# DigitalandPWR.net
KiCad netlist of a schematic drawn in Altium Designer
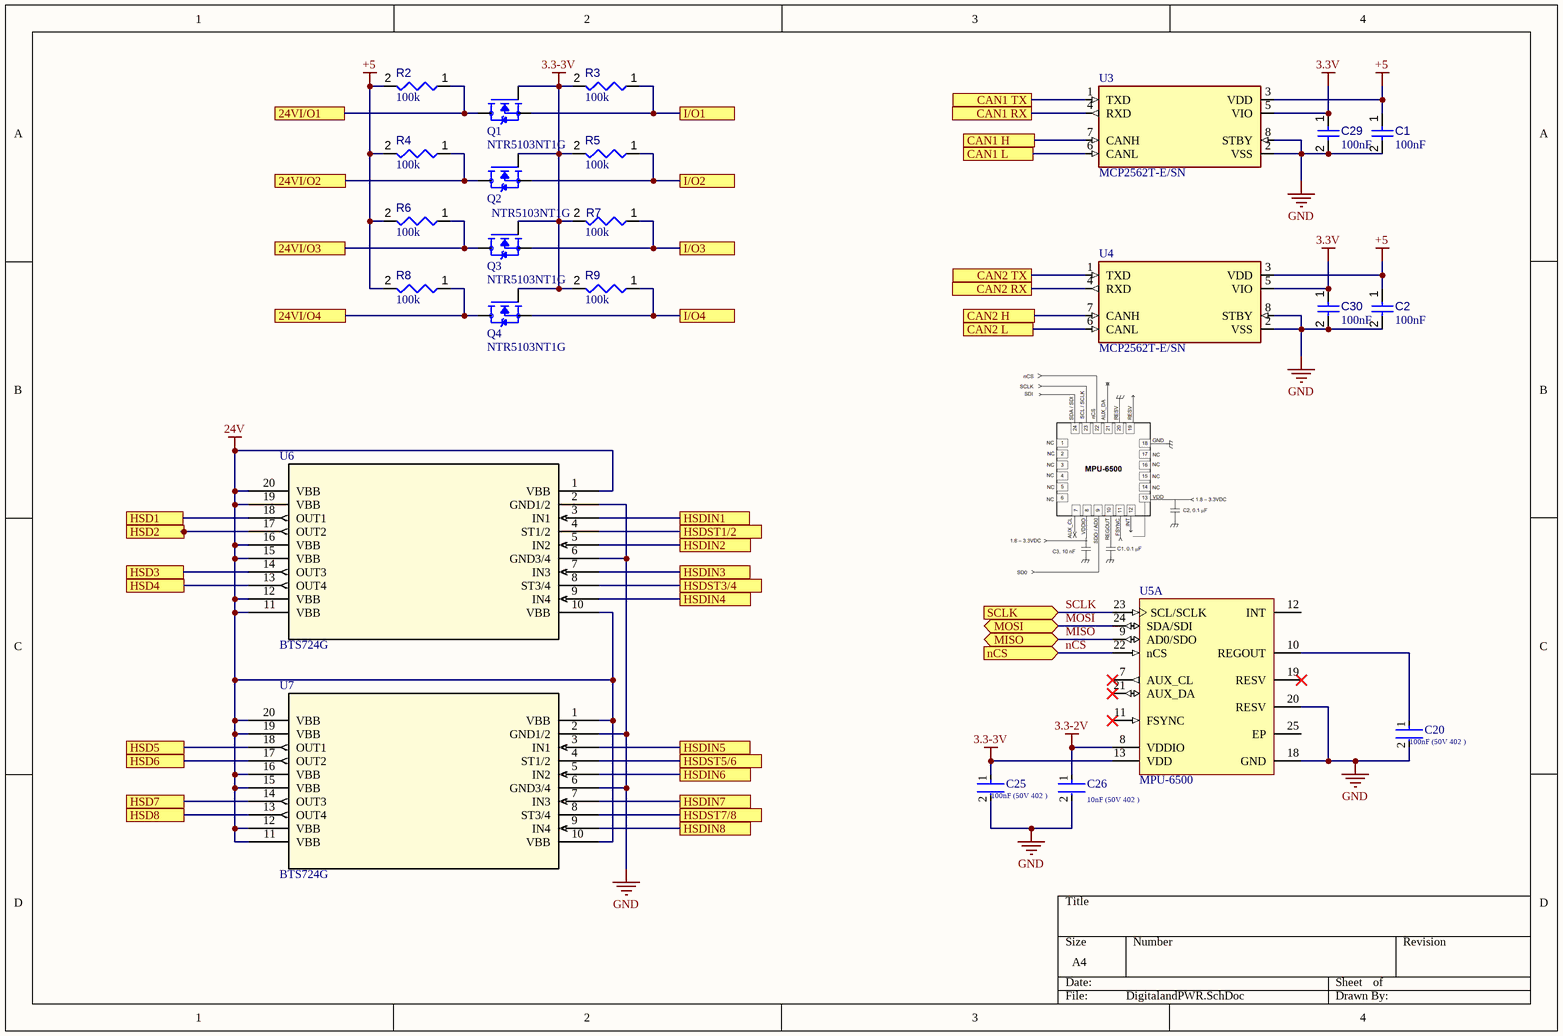
[diagram p0: DigitalandPWR.SchDoc]

(export (version "E")
  (design (tool "Eeschema 10.0.6"))
  (components
    (comp (ref "C1")
      (value "100nF")
      (footprint "CAPC0402(1005)60_L")
      (description "Chip Capacitor, 100nF +/-20%, 25V, 0402, Thickness 0.6 mm")
      (fields (field (name "TOLERANCE") "10%") (field (name "Comment") "Capacitor 100nF +/-20% 25V 0402"))
      (libsource (lib "Western Formula Racing") (part "CAP-NP-2"))
    )
    (comp (ref "C2")
      (value "100nF")
      (footprint "CAPC0402(1005)60_L")
      (description "Chip Capacitor, 100nF +/-20%, 25V, 0402, Thickness 0.6 mm")
      (fields (field (name "TOLERANCE") "10%") (field (name "Comment") "Capacitor 100nF +/-20% 25V 0402"))
      (libsource (lib "Western Formula Racing") (part "CAP-NP-2"))
    )
    (comp (ref "C20")
      (value "100nF (50V 402 )")
      (footprint "FP-CL779-IPC_C")
      (description "Cap Ceramic 100nF 50V X7R ±10% SMD 0402 +125°C Paper T/R")
      (libsource (lib "Altium Content Vault") (part "b4654b650e69147ec39a6b967a45e02"))
    )
    (comp (ref "C25")
      (value "100nF (50V 402 )")
      (footprint "FP-CL779-IPC_C")
      (description "Cap Ceramic 100nF 50V X7R ±10% SMD 0402 +125°C Paper T/R")
      (libsource (lib "Altium Content Vault") (part "b4654b650e69147ec39a6b967a45e02"))
    )
    (comp (ref "C26")
      (value "10nF (50V 402 )")
      (footprint "FP-CL165-IPC_C")
      (description "Cap Ceramic 10nF 50V X7R ±10% SMD 0402 +125°C Paper T/R")
      (fields (field (name "VOLTAGE") "50V") (field (name "TOLERANCE") "10%"))
      (libsource (lib "Altium Content Vault") (part "b4654b650e69147ec39a6b967a45e02"))
    )
    (comp (ref "C29")
      (value "100nF")
      (footprint "CAPC0402(1005)60_L")
      (description "Chip Capacitor, 100nF +/-20%, 25V, 0402, Thickness 0.6 mm")
      (fields (field (name "TOLERANCE") "10%") (field (name "Comment") "Capacitor 100nF +/-20% 25V 0402"))
      (libsource (lib "Western Formula Racing") (part "CAP-NP-2"))
    )
    (comp (ref "C30")
      (value "100nF")
      (footprint "CAPC0402(1005)60_L")
      (description "Chip Capacitor, 100nF +/-20%, 25V, 0402, Thickness 0.6 mm")
      (fields (field (name "TOLERANCE") "10%") (field (name "Comment") "Capacitor 100nF +/-20% 25V 0402"))
      (libsource (lib "Western Formula Racing") (part "CAP-NP-2"))
    )
    (comp (ref "Q1")
      (value "NTR5103NT1G")
      (footprint "SOT95P237X111-3N")
      (description "N-Channel 60V 260mA _Ta_ 300mW _Ta_ Surface Mount SOT-23-3 _TO-236_")
      (fields (field (name "MF") "ON Semiconductor"))
      (libsource (lib "Western Formula Racing") (part "NTR5103NT1G"))
    )
    (comp (ref "Q2")
      (value "NTR5103NT1G")
      (footprint "SOT95P237X111-3N")
      (description "N-Channel 60V 260mA _Ta_ 300mW _Ta_ Surface Mount SOT-23-3 _TO-236_")
      (fields (field (name "MF") "ON Semiconductor"))
      (libsource (lib "Western Formula Racing") (part "NTR5103NT1G"))
    )
    (comp (ref "Q3")
      (value "NTR5103NT1G")
      (footprint "SOT95P237X111-3N")
      (description "N-Channel 60V 260mA _Ta_ 300mW _Ta_ Surface Mount SOT-23-3 _TO-236_")
      (fields (field (name "MF") "ON Semiconductor"))
      (libsource (lib "Western Formula Racing") (part "NTR5103NT1G"))
    )
    (comp (ref "Q4")
      (value "NTR5103NT1G")
      (footprint "SOT95P237X111-3N")
      (description "N-Channel 60V 260mA _Ta_ 300mW _Ta_ Surface Mount SOT-23-3 _TO-236_")
      (fields (field (name "MF") "ON Semiconductor"))
      (libsource (lib "Western Formula Racing") (part "NTR5103NT1G"))
    )
    (comp (ref "R2")
      (value "100k")
      (footprint "RESC0402(1005)_L")
      (description "Chip Resistor, 100 kOhms, +/-1 %, 63 mW, -55 to 155 degC, 0402")
      (fields (field (name "TOLERANCE") "1%") (field (name "POWER") "63mW"))
      (libsource (lib "Western Formula Racing") (part "RES-2"))
    )
    (comp (ref "R3")
      (value "100k")
      (footprint "RESC0402(1005)_L")
      (description "Chip Resistor, 100 kOhms, +/-1 %, 63 mW, -55 to 155 degC, 0402")
      (fields (field (name "TOLERANCE") "1%") (field (name "POWER") "63mW"))
      (libsource (lib "Western Formula Racing") (part "RES-2"))
    )
    (comp (ref "R4")
      (value "100k")
      (footprint "RESC0402(1005)_L")
      (description "Chip Resistor, 100 kOhms, +/-1 %, 63 mW, -55 to 155 degC, 0402")
      (fields (field (name "TOLERANCE") "1%") (field (name "POWER") "63mW"))
      (libsource (lib "Western Formula Racing") (part "RES-2"))
    )
    (comp (ref "R5")
      (value "100k")
      (footprint "RESC0402(1005)_L")
      (description "Chip Resistor, 100 kOhms, +/-1 %, 63 mW, -55 to 155 degC, 0402")
      (fields (field (name "TOLERANCE") "1%") (field (name "POWER") "63mW"))
      (libsource (lib "Western Formula Racing") (part "RES-2"))
    )
    (comp (ref "R6")
      (value "100k")
      (footprint "RESC0402(1005)_L")
      (description "Chip Resistor, 100 kOhms, +/-1 %, 63 mW, -55 to 155 degC, 0402")
      (fields (field (name "TOLERANCE") "1%") (field (name "POWER") "63mW"))
      (libsource (lib "Western Formula Racing") (part "RES-2"))
    )
    (comp (ref "R7")
      (value "100k")
      (footprint "RESC0402(1005)_L")
      (description "Chip Resistor, 100 kOhms, +/-1 %, 63 mW, -55 to 155 degC, 0402")
      (fields (field (name "TOLERANCE") "1%") (field (name "POWER") "63mW"))
      (libsource (lib "Western Formula Racing") (part "RES-2"))
    )
    (comp (ref "R8")
      (value "100k")
      (footprint "RESC0402(1005)_L")
      (description "Chip Resistor, 100 kOhms, +/-1 %, 63 mW, -55 to 155 degC, 0402")
      (fields (field (name "TOLERANCE") "1%") (field (name "POWER") "63mW"))
      (libsource (lib "Western Formula Racing") (part "RES-2"))
    )
    (comp (ref "R9")
      (value "100k")
      (footprint "RESC0402(1005)_L")
      (description "Chip Resistor, 100 kOhms, +/-1 %, 63 mW, -55 to 155 degC, 0402")
      (fields (field (name "TOLERANCE") "1%") (field (name "POWER") "63mW"))
      (libsource (lib "Western Formula Racing") (part "RES-2"))
    )
    (comp (ref "U3")
      (value "MCP2562T-E/SN")
      (footprint "SOIC127P600X175-8N")
      (description "1/1 Transceiver Half CANbus 8-SOIC")
      (fields (field (name "DIGI-KEY_PART_NUMBER") "MCP2562T-E/SNCT-ND") (field (name "MF") "Microchip"))
      (libsource (lib "Western Formula Racing") (part "MCP2562T-E/SN"))
    )
    (comp (ref "U4")
      (value "MCP2562T-E/SN")
      (footprint "SOIC127P600X175-8N")
      (description "1/1 Transceiver Half CANbus 8-SOIC")
      (fields (field (name "DIGI-KEY_PART_NUMBER") "MCP2562T-E/SNCT-ND") (field (name "MF") "Microchip"))
      (libsource (lib "Western Formula Racing") (part "MCP2562T-E/SN"))
    )
    (comp (ref "U5")
      (value "MPU-6500")
      (footprint "INSE-MPU-6500-QFN24_M")
      (fields (field (name "MANUFACTURER") "InvenSense"))
      (libsource (lib "Altium Content Vault") (part "INSE-MPU-6500-24"))
    )
    (comp (ref "U6")
      (value "BTS724G")
      (footprint "SOIC-20_INF")
      (description "No Description Available")
      (fields (field (name "COPYRIGHT") "Copyright (C) 2023 Ultra Librarian. All rights reserved."))
      (libsource (lib "Western Formula Racing") (part "BTS724G"))
    )
    (comp (ref "U7")
      (value "BTS724G")
      (footprint "SOIC-20_INF")
      (description "No Description Available")
      (fields (field (name "COPYRIGHT") "Copyright (C) 2023 Ultra Librarian. All rights reserved."))
      (libsource (lib "Western Formula Racing") (part "BTS724G"))
    )
  )
  (nets
    (net (code "1") (name "+5") (class "Default")
      (node (ref "C1") (pin "1") (pinfunction "1_1") (pintype "passive"))
      (node (ref "C2") (pin "1") (pinfunction "1_1") (pintype "passive"))
      (node (ref "R2") (pin "2") (pinfunction "2_2") (pintype "passive"))
      (node (ref "R4") (pin "2") (pinfunction "2_2") (pintype "passive"))
      (node (ref "R6") (pin "2") (pinfunction "2_2") (pintype "passive"))
      (node (ref "R8") (pin "2") (pinfunction "2_2") (pintype "passive"))
      (node (ref "U3") (pin "3") (pinfunction "VDD_3") (pintype "power_in"))
      (node (ref "U4") (pin "3") (pinfunction "VDD_3") (pintype "power_in"))
    )
    (net (code "2") (name "/24VI{slash}O1") (class "Default")
      (node (ref "Q1") (pin "3") (pinfunction "D_3") (pintype "passive"))
      (node (ref "R2") (pin "1") (pinfunction "1_1") (pintype "passive"))
    )
    (net (code "3") (name "/24VI{slash}O2") (class "Default")
      (node (ref "Q2") (pin "3") (pinfunction "D_3") (pintype "passive"))
      (node (ref "R4") (pin "1") (pinfunction "1_1") (pintype "passive"))
    )
    (net (code "4") (name "/24VI{slash}O3") (class "Default")
      (node (ref "Q3") (pin "3") (pinfunction "D_3") (pintype "passive"))
      (node (ref "R6") (pin "1") (pinfunction "1_1") (pintype "passive"))
    )
    (net (code "5") (name "/24VI{slash}O4") (class "Default")
      (node (ref "Q4") (pin "3") (pinfunction "D_3") (pintype "passive"))
      (node (ref "R8") (pin "1") (pinfunction "1_1") (pintype "passive"))
    )
    (net (code "6") (name "/CAN1 H") (class "Default")
      (node (ref "U3") (pin "7") (pinfunction "CANH_7") (pintype "input"))
    )
    (net (code "7") (name "/CAN1 L") (class "Default")
      (node (ref "U3") (pin "6") (pinfunction "CANL_6") (pintype "input"))
    )
    (net (code "8") (name "/CAN1 RX") (class "Default")
      (node (ref "U3") (pin "4") (pinfunction "RXD_4") (pintype "output"))
    )
    (net (code "9") (name "/CAN1 TX") (class "Default")
      (node (ref "U3") (pin "1") (pinfunction "TXD_1") (pintype "input"))
    )
    (net (code "10") (name "/CAN2 H") (class "Default")
      (node (ref "U4") (pin "7") (pinfunction "CANH_7") (pintype "input"))
    )
    (net (code "11") (name "/CAN2 L") (class "Default")
      (node (ref "U4") (pin "6") (pinfunction "CANL_6") (pintype "input"))
    )
    (net (code "12") (name "/CAN2 RX") (class "Default")
      (node (ref "U4") (pin "4") (pinfunction "RXD_4") (pintype "output"))
    )
    (net (code "13") (name "/CAN2 TX") (class "Default")
      (node (ref "U4") (pin "1") (pinfunction "TXD_1") (pintype "input"))
    )
    (net (code "14") (name "/HSD1") (class "Default")
      (node (ref "U6") (pin "18") (pinfunction "OUT1_18") (pintype "output"))
    )
    (net (code "15") (name "/HSD2") (class "Default")
      (node (ref "U6") (pin "17") (pinfunction "OUT2_17") (pintype "output"))
    )
    (net (code "16") (name "/HSD3") (class "Default")
      (node (ref "U6") (pin "14") (pinfunction "OUT3_14") (pintype "output"))
    )
    (net (code "17") (name "/HSD4") (class "Default")
      (node (ref "U6") (pin "13") (pinfunction "OUT4_13") (pintype "output"))
    )
    (net (code "18") (name "/HSD5") (class "Default")
      (node (ref "U7") (pin "18") (pinfunction "OUT1_18") (pintype "output"))
    )
    (net (code "19") (name "/HSD6") (class "Default")
      (node (ref "U7") (pin "17") (pinfunction "OUT2_17") (pintype "output"))
    )
    (net (code "20") (name "/HSD7") (class "Default")
      (node (ref "U7") (pin "14") (pinfunction "OUT3_14") (pintype "output"))
    )
    (net (code "21") (name "/HSD8") (class "Default")
      (node (ref "U7") (pin "13") (pinfunction "OUT4_13") (pintype "output"))
    )
    (net (code "22") (name "/HSDIN1") (class "Default")
      (node (ref "U6") (pin "3") (pinfunction "IN1_3") (pintype "input"))
    )
    (net (code "23") (name "/HSDIN2") (class "Default")
      (node (ref "U6") (pin "5") (pinfunction "IN2_5") (pintype "input"))
    )
    (net (code "24") (name "/HSDIN3") (class "Default")
      (node (ref "U6") (pin "7") (pinfunction "IN3_7") (pintype "input"))
    )
    (net (code "25") (name "/HSDIN4") (class "Default")
      (node (ref "U6") (pin "9") (pinfunction "IN4_9") (pintype "input"))
    )
    (net (code "26") (name "/HSDIN5") (class "Default")
      (node (ref "U7") (pin "3") (pinfunction "IN1_3") (pintype "input"))
    )
    (net (code "27") (name "/HSDIN6") (class "Default")
      (node (ref "U7") (pin "5") (pinfunction "IN2_5") (pintype "input"))
    )
    (net (code "28") (name "/HSDIN7") (class "Default")
      (node (ref "U7") (pin "7") (pinfunction "IN3_7") (pintype "input"))
    )
    (net (code "29") (name "/HSDIN8") (class "Default")
      (node (ref "U7") (pin "9") (pinfunction "IN4_9") (pintype "input"))
    )
    (net (code "30") (name "/HSDST1{slash}2") (class "Default")
      (node (ref "U6") (pin "4") (pinfunction "ST1/2_4") (pintype "passive"))
    )
    (net (code "31") (name "/HSDST3{slash}4") (class "Default")
      (node (ref "U6") (pin "8") (pinfunction "ST3/4_8") (pintype "passive"))
    )
    (net (code "32") (name "/HSDST5{slash}6") (class "Default")
      (node (ref "U7") (pin "4") (pinfunction "ST1/2_4") (pintype "passive"))
    )
    (net (code "33") (name "/HSDST7{slash}8") (class "Default")
      (node (ref "U7") (pin "8") (pinfunction "ST3/4_8") (pintype "passive"))
    )
    (net (code "34") (name "/I{slash}O1") (class "Default")
      (node (ref "Q1") (pin "2") (pinfunction "S_2") (pintype "passive"))
      (node (ref "R3") (pin "1") (pinfunction "1_1") (pintype "passive"))
    )
    (net (code "35") (name "/I{slash}O2") (class "Default")
      (node (ref "Q2") (pin "2") (pinfunction "S_2") (pintype "passive"))
      (node (ref "R5") (pin "1") (pinfunction "1_1") (pintype "passive"))
    )
    (net (code "36") (name "/I{slash}O3") (class "Default")
      (node (ref "Q3") (pin "2") (pinfunction "S_2") (pintype "passive"))
      (node (ref "R7") (pin "1") (pinfunction "1_1") (pintype "passive"))
    )
    (net (code "37") (name "/I{slash}O4") (class "Default")
      (node (ref "Q4") (pin "2") (pinfunction "S_2") (pintype "passive"))
      (node (ref "R9") (pin "1") (pinfunction "1_1") (pintype "passive"))
    )
    (net (code "38") (name "/MISO") (class "Default")
      (node (ref "U5") (pin "9") (pinfunction "AD0/SDO_9") (pintype "bidirectional"))
    )
    (net (code "39") (name "/MOSI") (class "Default")
      (node (ref "U5") (pin "24") (pinfunction "SDA/SDI_24") (pintype "bidirectional"))
    )
    (net (code "40") (name "/SCLK") (class "Default")
      (node (ref "U5") (pin "23") (pinfunction "SCL/SCLK_23") (pintype "input"))
    )
    (net (code "41") (name "/nCS") (class "Default")
      (node (ref "U5") (pin "22") (pinfunction "nCS_22") (pintype "input"))
    )
    (net (code "42") (name "3.3-2V") (class "Default")
      (node (ref "C26") (pin "1") (pinfunction "1_1") (pintype "passive"))
      (node (ref "U5") (pin "8") (pinfunction "VDDIO_8") (pintype "power_in"))
    )
    (net (code "43") (name "3.3-3V") (class "Default")
      (node (ref "C25") (pin "1") (pinfunction "1_1") (pintype "passive"))
      (node (ref "Q1") (pin "1") (pinfunction "G_1") (pintype "passive"))
      (node (ref "Q2") (pin "1") (pinfunction "G_1") (pintype "passive"))
      (node (ref "Q3") (pin "1") (pinfunction "G_1") (pintype "passive"))
      (node (ref "Q4") (pin "1") (pinfunction "G_1") (pintype "passive"))
      (node (ref "R3") (pin "2") (pinfunction "2_2") (pintype "passive"))
      (node (ref "R5") (pin "2") (pinfunction "2_2") (pintype "passive"))
      (node (ref "R7") (pin "2") (pinfunction "2_2") (pintype "passive"))
      (node (ref "R9") (pin "2") (pinfunction "2_2") (pintype "passive"))
      (node (ref "U5") (pin "13") (pinfunction "VDD_13") (pintype "power_in"))
    )
    (net (code "44") (name "3.3V") (class "Default")
      (node (ref "C29") (pin "1") (pinfunction "1_1") (pintype "passive"))
      (node (ref "C30") (pin "1") (pinfunction "1_1") (pintype "passive"))
      (node (ref "U3") (pin "5") (pinfunction "VIO_5") (pintype "power_in"))
      (node (ref "U4") (pin "5") (pinfunction "VIO_5") (pintype "power_in"))
    )
    (net (code "45") (name "24V") (class "Default")
      (node (ref "U6") (pin "1") (pinfunction "VBB_1") (pintype "power_in"))
      (node (ref "U6") (pin "10") (pinfunction "VBB_10") (pintype "power_in"))
      (node (ref "U6") (pin "11") (pinfunction "VBB_11") (pintype "power_in"))
      (node (ref "U6") (pin "12") (pinfunction "VBB_12") (pintype "power_in"))
      (node (ref "U6") (pin "15") (pinfunction "VBB_15") (pintype "power_in"))
      (node (ref "U6") (pin "16") (pinfunction "VBB_16") (pintype "power_in"))
      (node (ref "U6") (pin "19") (pinfunction "VBB_19") (pintype "power_in"))
      (node (ref "U6") (pin "20") (pinfunction "VBB_20") (pintype "power_in"))
      (node (ref "U7") (pin "1") (pinfunction "VBB_1") (pintype "power_in"))
      (node (ref "U7") (pin "10") (pinfunction "VBB_10") (pintype "power_in"))
      (node (ref "U7") (pin "11") (pinfunction "VBB_11") (pintype "power_in"))
      (node (ref "U7") (pin "12") (pinfunction "VBB_12") (pintype "power_in"))
      (node (ref "U7") (pin "15") (pinfunction "VBB_15") (pintype "power_in"))
      (node (ref "U7") (pin "16") (pinfunction "VBB_16") (pintype "power_in"))
      (node (ref "U7") (pin "19") (pinfunction "VBB_19") (pintype "power_in"))
      (node (ref "U7") (pin "20") (pinfunction "VBB_20") (pintype "power_in"))
    )
    (net (code "46") (name "GND") (class "Default")
      (node (ref "C1") (pin "2") (pinfunction "2_2") (pintype "passive"))
      (node (ref "C2") (pin "2") (pinfunction "2_2") (pintype "passive"))
      (node (ref "C20") (pin "2") (pinfunction "2_2") (pintype "passive"))
      (node (ref "C25") (pin "2") (pinfunction "2_2") (pintype "passive"))
      (node (ref "C26") (pin "2") (pinfunction "2_2") (pintype "passive"))
      (node (ref "C29") (pin "2") (pinfunction "2_2") (pintype "passive"))
      (node (ref "C30") (pin "2") (pinfunction "2_2") (pintype "passive"))
      (node (ref "U3") (pin "2") (pinfunction "VSS_2") (pintype "power_in"))
      (node (ref "U3") (pin "8") (pinfunction "STBY_8") (pintype "input"))
      (node (ref "U4") (pin "2") (pinfunction "VSS_2") (pintype "power_in"))
      (node (ref "U4") (pin "8") (pinfunction "STBY_8") (pintype "input"))
      (node (ref "U5") (pin "18") (pinfunction "GND_18") (pintype "power_in"))
      (node (ref "U5") (pin "20") (pinfunction "RESV_20") (pintype "power_in"))
      (node (ref "U6") (pin "2") (pinfunction "GND1/2_2") (pintype "power_in"))
      (node (ref "U6") (pin "6") (pinfunction "GND3/4_6") (pintype "power_in"))
      (node (ref "U7") (pin "2") (pinfunction "GND1/2_2") (pintype "power_in"))
      (node (ref "U7") (pin "6") (pinfunction "GND3/4_6") (pintype "power_in"))
    )
    (net (code "47") (name "Net-(U5A-REGOUT)") (class "Default")
      (node (ref "C20") (pin "1") (pinfunction "1_1") (pintype "passive"))
      (node (ref "U5") (pin "10") (pinfunction "REGOUT_10") (pintype "passive"))
    )
    (net (code "48") (name "unconnected-(U5A-AUX_CL-Pad7)") (class "Default")
      (node (ref "U5") (pin "7") (pinfunction "AUX_CL_7") (pintype "output+no_connect"))
    )
    (net (code "49") (name "unconnected-(U5A-AUX_DA-Pad21)") (class "Default")
      (node (ref "U5") (pin "21") (pinfunction "AUX_DA_21") (pintype "bidirectional+no_connect"))
    )
    (net (code "50") (name "unconnected-(U5A-EP-Pad25)") (class "Default")
      (node (ref "U5") (pin "25") (pinfunction "EP_25") (pintype "passive"))
    )
    (net (code "51") (name "unconnected-(U5A-FSYNC-Pad11)") (class "Default")
      (node (ref "U5") (pin "11") (pinfunction "FSYNC_11") (pintype "input+no_connect"))
    )
    (net (code "52") (name "unconnected-(U5A-INT-Pad12)") (class "Default")
      (node (ref "U5") (pin "12") (pinfunction "INT_12") (pintype "open_collector"))
    )
    (net (code "53") (name "unconnected-(U5A-RESV-Pad19)") (class "Default")
      (node (ref "U5") (pin "19") (pinfunction "RESV_19") (pintype "passive+no_connect"))
    )
  )
)
